# main.net
KiCad netlist of a schematic drawn in Altium Designer
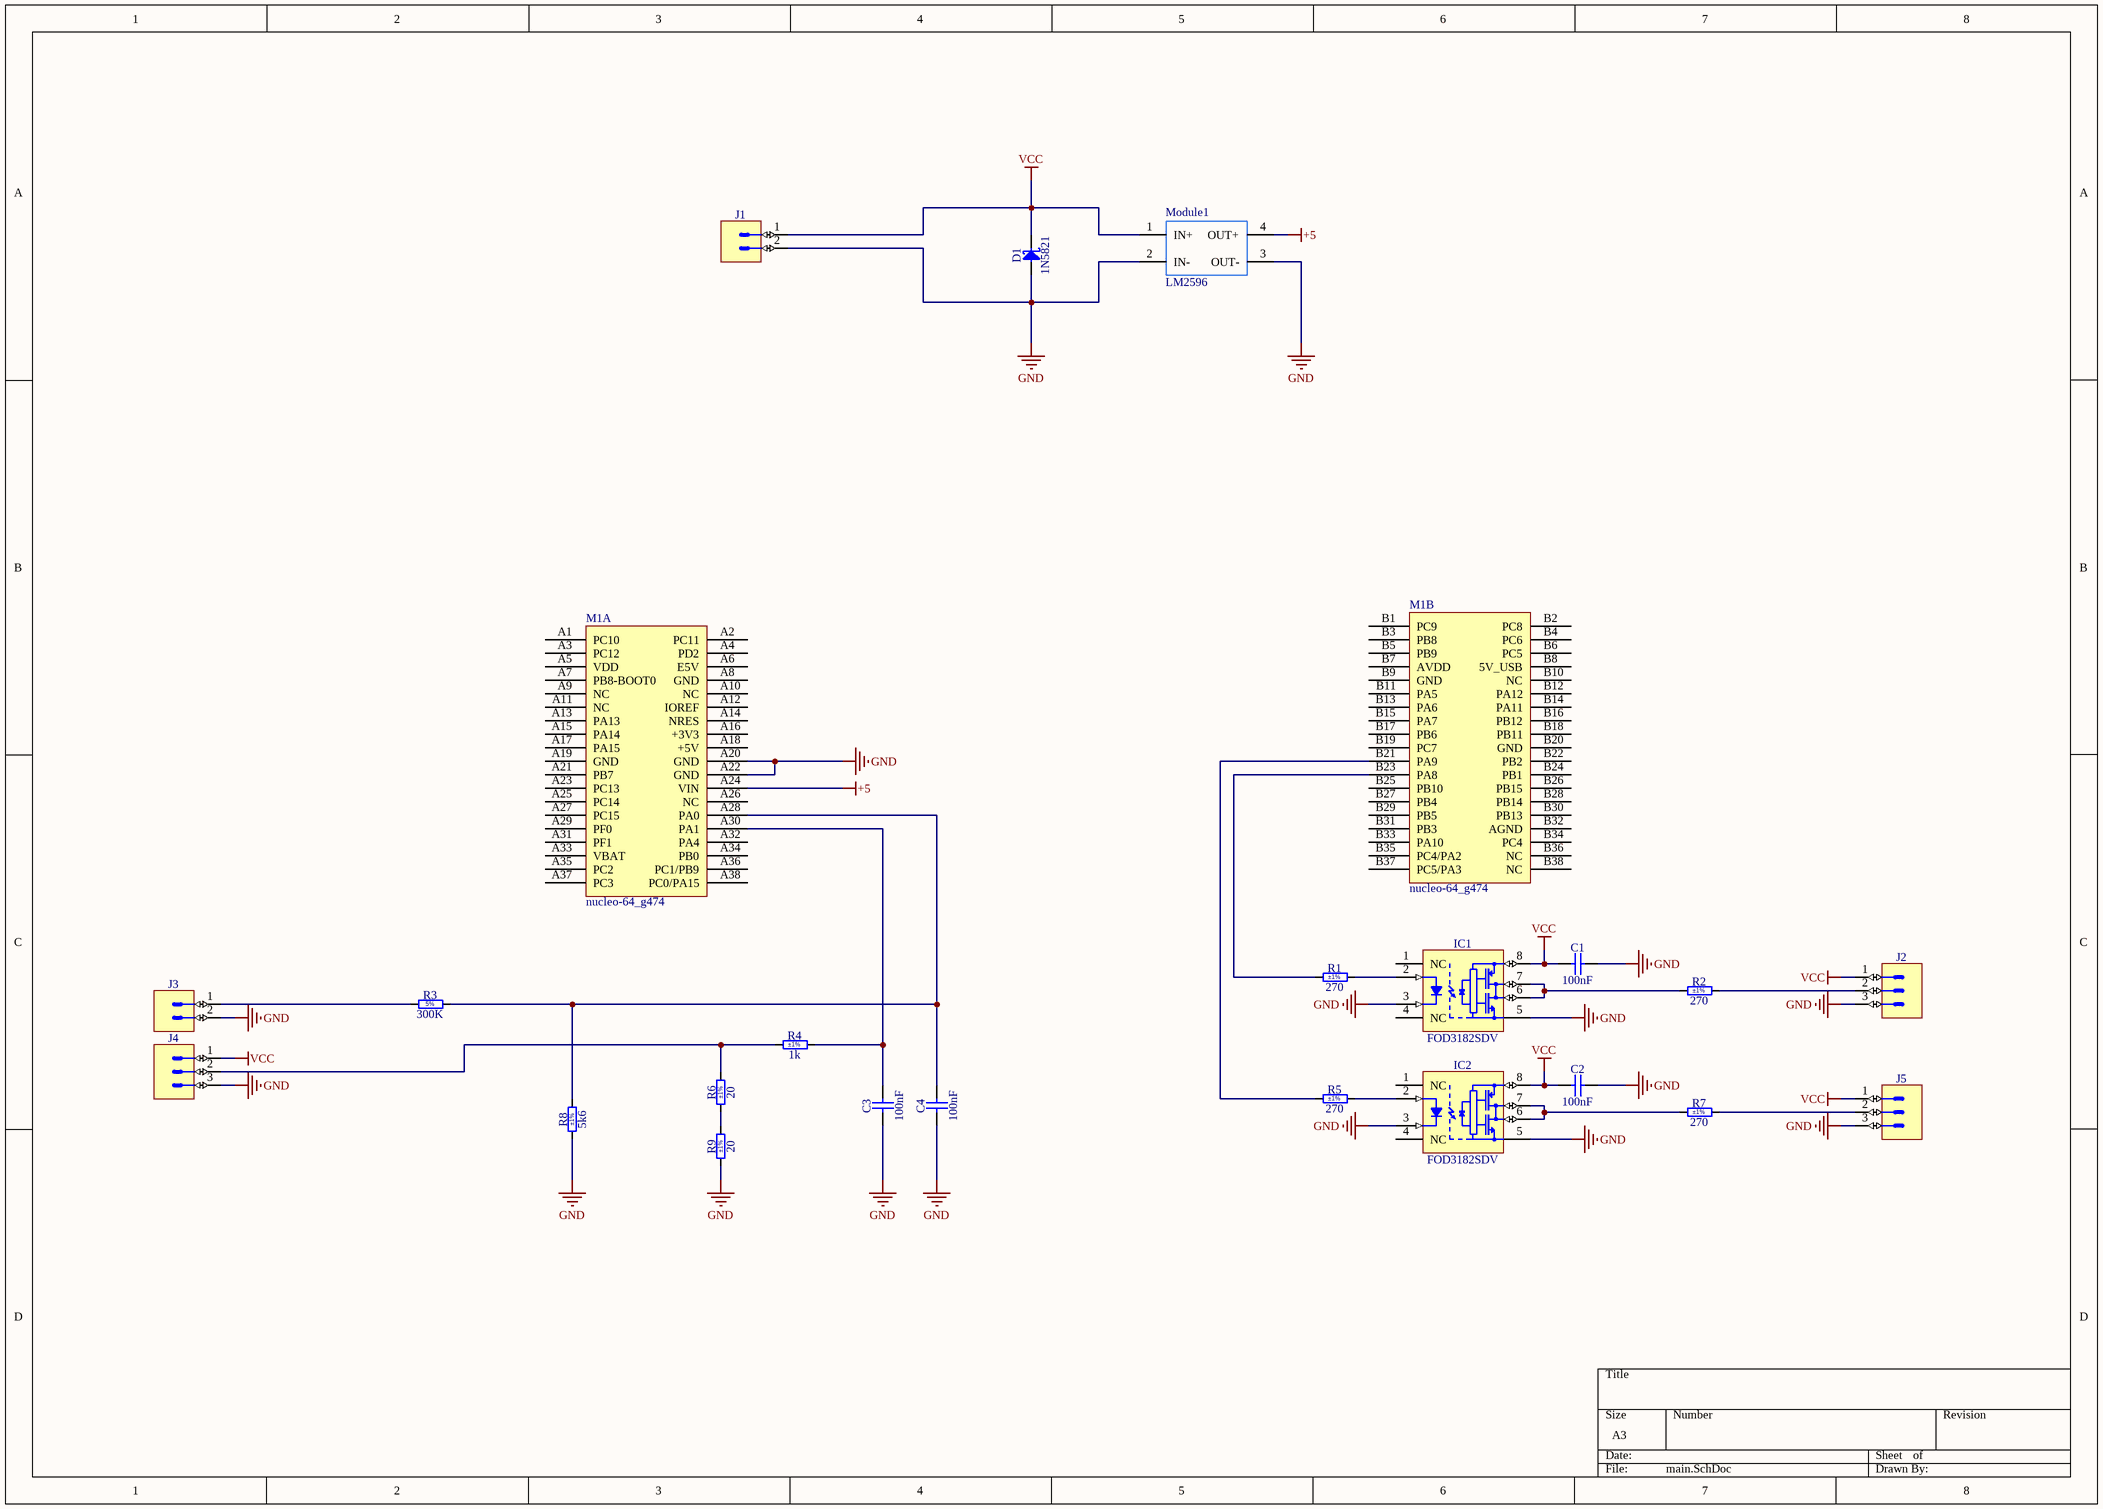
[diagram p0: main.SchDoc]

(export (version "E")
  (design (tool "Eeschema 10.0.6"))
  (components
    (comp (ref "C1")
      (value "100nF")
      (footprint "CAPRR508-350X500X500")
      (description "Non-polarised capacitor")
      (fields
        (field (name "PART NUMBER") "CCR_100NF_50V_10%_X7R_508-350X500X500")
        (field (name "VOLTAGE") "50VDC")
        (field (name "AUTHOR") "CERN DEM JLC")
      )
      (libsource (lib "Capacitors") (part "Capacitor - non polarized"))
    )
    (comp (ref "C2")
      (value "100nF")
      (footprint "CAPRR508-350X500X500")
      (description "Non-polarised capacitor")
      (fields
        (field (name "PART NUMBER") "CCR_100NF_50V_10%_X7R_508-350X500X500")
        (field (name "VOLTAGE") "50VDC")
        (field (name "AUTHOR") "CERN DEM JLC")
      )
      (libsource (lib "Capacitors") (part "Capacitor - non polarized"))
    )
    (comp (ref "C3")
      (value "100nF")
      (footprint "CAPRR508-350X500X500")
      (description "Non-polarised capacitor")
      (fields
        (field (name "PART NUMBER") "CCR_100NF_50V_10%_X7R_508-350X500X500")
        (field (name "VOLTAGE") "50VDC")
        (field (name "AUTHOR") "CERN DEM JLC")
      )
      (libsource (lib "Capacitors") (part "Capacitor - non polarized"))
    )
    (comp (ref "C4")
      (value "100nF")
      (footprint "CAPRR508-350X500X500")
      (description "Non-polarised capacitor")
      (fields
        (field (name "PART NUMBER") "CCR_100NF_50V_10%_X7R_508-350X500X500")
        (field (name "VOLTAGE") "50VDC")
        (field (name "AUTHOR") "CERN DEM JLC")
      )
      (libsource (lib "Capacitors") (part "Capacitor - non polarized"))
    )
    (comp (ref "D1")
      (value "1N5821")
      (footprint "DO-201AD")
      (description "Schottky Diode")
      (fields
        (field (name "VOLTAGE") "30V")
        (field (name "POWER") "3A")
        (field (name "AUTHOR") "CERN DEM JLC")
      )
      (libsource (lib "ICs And Semiconductors") (part "Diode Schottky"))
    )
    (comp (ref "IC1")
      (value "FOD3182SDV")
      (footprint "FAIRCHILD_8LD MDIP (OPTION S)")
      (description "Optocoupler")
      (fields (field (name "MANUFACTURER") "FAIRCHILD SEMICONDUCTOR") (field (name "AUTHOR") "CERN DEM JLC"))
      (libsource (lib "ICs And Semiconductors") (part "Optocoupler Type17"))
    )
    (comp (ref "IC2")
      (value "FOD3182SDV")
      (footprint "FAIRCHILD_8LD MDIP (OPTION S)")
      (description "Optocoupler")
      (fields (field (name "MANUFACTURER") "FAIRCHILD SEMICONDUCTOR") (field (name "AUTHOR") "CERN DEM JLC"))
      (libsource (lib "ICs And Semiconductors") (part "Optocoupler Type17"))
    )
    (comp (ref "J1")
      (value "~")
      (footprint "PHOENIX_1757242")
      (description "Connector 2 Male")
      (fields
        (field (name "PART NUMBER") "PHOENIX_1757242")
        (field (name "MANUFACTURER") "PHOENIX CONTACT")
        (field (name "AUTHOR") "CERN DEM JLC")
      )
      (libsource (lib "Connectors") (part "Connector 2 Male"))
    )
    (comp (ref "J2")
      (value "~")
      (footprint "PHOENIX_1757255")
      (description "Connector 3 Male")
      (fields
        (field (name "PART NUMBER") "PHOENIX_1757255")
        (field (name "MANUFACTURER") "PHOENIX CONTACT")
        (field (name "AUTHOR") "CERN DEM JLC")
      )
      (libsource (lib "") (part "Connector 3 Male_1"))
    )
    (comp (ref "J3")
      (value "~")
      (footprint "PHOENIX_1757242")
      (description "Connector 2 Male")
      (fields
        (field (name "PART NUMBER") "PHOENIX_1757242")
        (field (name "MANUFACTURER") "PHOENIX CONTACT")
        (field (name "AUTHOR") "CERN DEM JLC")
      )
      (libsource (lib "Connectors") (part "Connector 2 Male"))
    )
    (comp (ref "J4")
      (value "~")
      (footprint "PHOENIX_1757255")
      (description "Connector 3 Male")
      (fields
        (field (name "PART NUMBER") "PHOENIX_1757255")
        (field (name "MANUFACTURER") "PHOENIX CONTACT")
        (field (name "AUTHOR") "CERN DEM JLC")
      )
      (libsource (lib "Connectors") (part "Connector 3 Male"))
    )
    (comp (ref "J5")
      (value "~")
      (footprint "PHOENIX_1757255")
      (description "Connector 3 Male")
      (fields
        (field (name "PART NUMBER") "PHOENIX_1757255")
        (field (name "MANUFACTURER") "PHOENIX CONTACT")
        (field (name "AUTHOR") "CERN DEM JLC")
      )
      (libsource (lib "") (part "Connector 3 Male_1"))
    )
    (comp (ref "M1")
      (value "nucleo-64_g474")
      (footprint "nucleo-64_g474:nucleo-64_g474")
      (libsource (lib "nucleo-64_g474") (part "nucleo-64_g474"))
    )
    (comp (ref "Module1") (value "LM2596") (footprint "DC_DC:DCDC") (libsource (lib "DC_DC") (part "LM2596")))
    (comp (ref "R1")
      (value "270")
      (footprint "RES1016-630X250")
      (description "Resistor - 1%")
      (fields
        (field (name "TOLERANCE") "±1%")
        (field (name "PART NUMBER") "RMF_270R_1%_0.6W_50PPM_1016-630X250")
        (field (name "POWER") "0.6W")
        (field (name "AUTHOR") "CERN DEM JLC")
      )
      (libsource (lib "Resistors") (part "Resistor - 1%"))
    )
    (comp (ref "R2")
      (value "270")
      (footprint "RES1016-630X250")
      (description "Resistor - 1%")
      (fields
        (field (name "TOLERANCE") "±1%")
        (field (name "PART NUMBER") "RMF_270R_1%_0.6W_50PPM_1016-630X250")
        (field (name "POWER") "0.6W")
        (field (name "AUTHOR") "CERN DEM JLC")
      )
      (libsource (lib "Resistors") (part "Resistor - 1%"))
    )
    (comp (ref "R3")
      (value "300K")
      (footprint "RES_PANASONIC_ERG5S")
      (description "Resistor - 5%")
      (fields
        (field (name "PART NUMBER") "RMF_100K_5%_5W_200PPM_PANASONIC_ERG5SJ104")
        (field (name "POWER") "5W")
        (field (name "AUTHOR") "CERN DEM BC")
      )
      (libsource (lib "Resistors") (part "Resistor - 5%"))
    )
    (comp (ref "R4")
      (value "1k")
      (footprint "RES1016-630X250")
      (description "Resistor - 1%")
      (fields
        (field (name "TOLERANCE") "±1%")
        (field (name "PART NUMBER") "RMF_1K_1%_0.6W_50PPM_1016-630X250")
        (field (name "POWER") "0.6W")
        (field (name "AUTHOR") "CERN DEM JLC")
      )
      (libsource (lib "Resistors") (part "Resistor - 1%"))
    )
    (comp (ref "R5")
      (value "270")
      (footprint "RES1016-630X250")
      (description "Resistor - 1%")
      (fields
        (field (name "TOLERANCE") "±1%")
        (field (name "PART NUMBER") "RMF_270R_1%_0.6W_50PPM_1016-630X250")
        (field (name "POWER") "0.6W")
        (field (name "AUTHOR") "CERN DEM JLC")
      )
      (libsource (lib "Resistors") (part "Resistor - 1%"))
    )
    (comp (ref "R6")
      (value "20")
      (footprint "RES1016-630X250")
      (description "Resistor - 1%")
      (fields
        (field (name "TOLERANCE") "±1%")
        (field (name "PART NUMBER") "RMF_120R_1%_0.6W_50PPM_1016-630X250")
        (field (name "POWER") "0.6W")
        (field (name "AUTHOR") "CERN DEM JLC")
      )
      (libsource (lib "Resistors") (part "Resistor - 1%"))
    )
    (comp (ref "R7")
      (value "270")
      (footprint "RES1016-630X250")
      (description "Resistor - 1%")
      (fields
        (field (name "TOLERANCE") "±1%")
        (field (name "PART NUMBER") "RMF_270R_1%_0.6W_50PPM_1016-630X250")
        (field (name "POWER") "0.6W")
        (field (name "AUTHOR") "CERN DEM JLC")
      )
      (libsource (lib "Resistors") (part "Resistor - 1%"))
    )
    (comp (ref "R8")
      (value "5k6")
      (footprint "RES1016-630X250")
      (description "Resistor - 1%")
      (fields
        (field (name "TOLERANCE") "±1%")
        (field (name "PART NUMBER") "RMF_5K6_1%_0.6W_50PPM_1016-630X250")
        (field (name "POWER") "0.6W")
        (field (name "AUTHOR") "CERN DEM JLC")
      )
      (libsource (lib "Resistors") (part "Resistor - 1%"))
    )
    (comp (ref "R9")
      (value "20")
      (footprint "RES1016-630X250")
      (description "Resistor - 1%")
      (fields
        (field (name "TOLERANCE") "±1%")
        (field (name "PART NUMBER") "RMF_120R_1%_0.6W_50PPM_1016-630X250")
        (field (name "POWER") "0.6W")
        (field (name "AUTHOR") "CERN DEM JLC")
      )
      (libsource (lib "Resistors") (part "Resistor - 1%"))
    )
  )
  (nets
    (net (code "1") (name "+5") (class "Default")
      (node (ref "M1") (pin "A24") (pinfunction "VIN_A24") (pintype "passive"))
      (node (ref "Module1") (pin "4") (pinfunction "OUT+_4") (pintype "passive"))
    )
    (net (code "2") (name "GND") (class "Default")
      (node (ref "C1") (pin "2") (pinfunction "2_2") (pintype "passive"))
      (node (ref "C2") (pin "2") (pinfunction "2_2") (pintype "passive"))
      (node (ref "C3") (pin "1") (pinfunction "1_1") (pintype "passive"))
      (node (ref "C4") (pin "1") (pinfunction "1_1") (pintype "passive"))
      (node (ref "D1") (pin "2") (pinfunction "A_2") (pintype "passive"))
      (node (ref "IC1") (pin "3") (pinfunction "K_3") (pintype "input"))
      (node (ref "IC1") (pin "5") (pinfunction "VSS_5") (pintype "power_in"))
      (node (ref "IC2") (pin "3") (pinfunction "K_3") (pintype "input"))
      (node (ref "IC2") (pin "5") (pinfunction "VSS_5") (pintype "power_in"))
      (node (ref "J1") (pin "2") (pinfunction "2_2") (pintype "bidirectional"))
      (node (ref "J2") (pin "3") (pinfunction "3_3") (pintype "bidirectional"))
      (node (ref "J3") (pin "2") (pinfunction "2_2") (pintype "bidirectional"))
      (node (ref "J4") (pin "3") (pinfunction "3_3") (pintype "bidirectional"))
      (node (ref "J5") (pin "3") (pinfunction "3_3") (pintype "bidirectional"))
      (node (ref "M1") (pin "A20") (pinfunction "GND_A20") (pintype "passive"))
      (node (ref "M1") (pin "A22") (pinfunction "GND_A22") (pintype "passive"))
      (node (ref "Module1") (pin "2") (pinfunction "IN-_2") (pintype "passive"))
      (node (ref "Module1") (pin "3") (pinfunction "OUT-_3") (pintype "passive"))
      (node (ref "R8") (pin "1") (pinfunction "1_1") (pintype "passive"))
      (node (ref "R9") (pin "1") (pinfunction "1_1") (pintype "passive"))
    )
    (net (code "3") (name "Net-(IC1-A)") (class "Default")
      (node (ref "IC1") (pin "2") (pinfunction "A_2") (pintype "input"))
      (node (ref "R1") (pin "2") (pinfunction "2_2") (pintype "passive"))
    )
    (net (code "4") (name "Net-(IC1-VO1)") (class "Default")
      (node (ref "IC1") (pin "6") (pinfunction "VO1_6") (pintype "bidirectional"))
      (node (ref "IC1") (pin "7") (pinfunction "VO2_7") (pintype "bidirectional"))
      (node (ref "R2") (pin "1") (pinfunction "1_1") (pintype "passive"))
    )
    (net (code "5") (name "Net-(IC2-A)") (class "Default")
      (node (ref "IC2") (pin "2") (pinfunction "A_2") (pintype "input"))
      (node (ref "R5") (pin "2") (pinfunction "2_2") (pintype "passive"))
    )
    (net (code "6") (name "Net-(IC2-VO1)") (class "Default")
      (node (ref "IC2") (pin "6") (pinfunction "VO1_6") (pintype "bidirectional"))
      (node (ref "IC2") (pin "7") (pinfunction "VO2_7") (pintype "bidirectional"))
      (node (ref "R7") (pin "1") (pinfunction "1_1") (pintype "passive"))
    )
    (net (code "7") (name "Net-(J2-Pad2)") (class "Default")
      (node (ref "J2") (pin "2") (pinfunction "2_2") (pintype "bidirectional"))
      (node (ref "R2") (pin "2") (pinfunction "2_2") (pintype "passive"))
    )
    (net (code "8") (name "Net-(J3-Pad1)") (class "Default")
      (node (ref "J3") (pin "1") (pinfunction "1_1") (pintype "bidirectional"))
      (node (ref "R3") (pin "1") (pinfunction "1_1") (pintype "passive"))
    )
    (net (code "9") (name "Net-(J4-Pad2)") (class "Default")
      (node (ref "J4") (pin "2") (pinfunction "2_2") (pintype "bidirectional"))
      (node (ref "R4") (pin "1") (pinfunction "1_1") (pintype "passive"))
      (node (ref "R6") (pin "2") (pinfunction "2_2") (pintype "passive"))
    )
    (net (code "10") (name "Net-(J5-Pad2)") (class "Default")
      (node (ref "J5") (pin "2") (pinfunction "2_2") (pintype "bidirectional"))
      (node (ref "R7") (pin "2") (pinfunction "2_2") (pintype "passive"))
    )
    (net (code "11") (name "Net-(M1A-PA0)") (class "Default")
      (node (ref "C4") (pin "2") (pinfunction "2_2") (pintype "passive"))
      (node (ref "M1") (pin "A28") (pinfunction "PA0_A28") (pintype "passive"))
      (node (ref "R3") (pin "2") (pinfunction "2_2") (pintype "passive"))
      (node (ref "R8") (pin "2") (pinfunction "2_2") (pintype "passive"))
    )
    (net (code "12") (name "Net-(M1A-PA1)") (class "Default")
      (node (ref "C3") (pin "2") (pinfunction "2_2") (pintype "passive"))
      (node (ref "M1") (pin "A30") (pinfunction "PA1_A30") (pintype "passive"))
      (node (ref "R4") (pin "2") (pinfunction "2_2") (pintype "passive"))
    )
    (net (code "13") (name "Net-(M1B-PA8)") (class "Default")
      (node (ref "M1") (pin "B23") (pinfunction "PA8_B23") (pintype "passive"))
      (node (ref "R1") (pin "1") (pinfunction "1_1") (pintype "passive"))
    )
    (net (code "14") (name "Net-(M1B-PA9)") (class "Default")
      (node (ref "M1") (pin "B21") (pinfunction "PA9_B21") (pintype "passive"))
      (node (ref "R5") (pin "1") (pinfunction "1_1") (pintype "passive"))
    )
    (net (code "15") (name "Net-(R6-Pad1)") (class "Default")
      (node (ref "R6") (pin "1") (pinfunction "1_1") (pintype "passive"))
      (node (ref "R9") (pin "2") (pinfunction "2_2") (pintype "passive"))
    )
    (net (code "16") (name "VCC") (class "Default")
      (node (ref "C1") (pin "1") (pinfunction "1_1") (pintype "passive"))
      (node (ref "C2") (pin "1") (pinfunction "1_1") (pintype "passive"))
      (node (ref "D1") (pin "1") (pinfunction "C_1") (pintype "passive"))
      (node (ref "IC1") (pin "8") (pinfunction "VDD_8") (pintype "bidirectional"))
      (node (ref "IC2") (pin "8") (pinfunction "VDD_8") (pintype "bidirectional"))
      (node (ref "J1") (pin "1") (pinfunction "1_1") (pintype "bidirectional"))
      (node (ref "J2") (pin "1") (pinfunction "1_1") (pintype "bidirectional"))
      (node (ref "J4") (pin "1") (pinfunction "1_1") (pintype "bidirectional"))
      (node (ref "J5") (pin "1") (pinfunction "1_1") (pintype "bidirectional"))
      (node (ref "Module1") (pin "1") (pinfunction "IN+_1") (pintype "passive"))
    )
    (net (code "17") (name "unconnected-(IC1-NC-Pad1)") (class "Default")
      (node (ref "IC1") (pin "1") (pinfunction "NC_1") (pintype "power_in"))
    )
    (net (code "18") (name "unconnected-(IC1-NC-Pad4)") (class "Default")
      (node (ref "IC1") (pin "4") (pinfunction "NC_4") (pintype "passive"))
    )
    (net (code "19") (name "unconnected-(IC2-NC-Pad1)") (class "Default")
      (node (ref "IC2") (pin "1") (pinfunction "NC_1") (pintype "power_in"))
    )
    (net (code "20") (name "unconnected-(IC2-NC-Pad4)") (class "Default")
      (node (ref "IC2") (pin "4") (pinfunction "NC_4") (pintype "passive"))
    )
    (net (code "21") (name "unconnected-(M1A-+3V3-PadA16)") (class "Default")
      (node (ref "M1") (pin "A16") (pinfunction "+3V3_A16") (pintype "passive"))
    )
    (net (code "22") (name "unconnected-(M1A-+5V-PadA18)") (class "Default")
      (node (ref "M1") (pin "A18") (pinfunction "+5V_A18") (pintype "passive"))
    )
    (net (code "23") (name "unconnected-(M1A-E5V-PadA6)") (class "Default")
      (node (ref "M1") (pin "A6") (pinfunction "E5V_A6") (pintype "passive"))
    )
    (net (code "24") (name "unconnected-(M1A-GND-PadA8)") (class "Default")
      (node (ref "M1") (pin "A8") (pinfunction "GND_A8") (pintype "passive"))
    )
    (net (code "25") (name "unconnected-(M1A-GND-PadA19)") (class "Default")
      (node (ref "M1") (pin "A19") (pinfunction "GND_A19") (pintype "passive"))
    )
    (net (code "26") (name "unconnected-(M1A-IOREF-PadA12)") (class "Default")
      (node (ref "M1") (pin "A12") (pinfunction "IOREF_A12") (pintype "passive"))
    )
    (net (code "27") (name "unconnected-(M1A-NC-PadA9)") (class "Default")
      (node (ref "M1") (pin "A9") (pinfunction "NC_A9") (pintype "passive"))
    )
    (net (code "28") (name "unconnected-(M1A-NC-PadA10)") (class "Default")
      (node (ref "M1") (pin "A10") (pinfunction "NC_A10") (pintype "passive"))
    )
    (net (code "29") (name "unconnected-(M1A-NC-PadA11)") (class "Default")
      (node (ref "M1") (pin "A11") (pinfunction "NC_A11") (pintype "passive"))
    )
    (net (code "30") (name "unconnected-(M1A-NC-PadA26)") (class "Default")
      (node (ref "M1") (pin "A26") (pinfunction "NC_A26") (pintype "passive"))
    )
    (net (code "31") (name "unconnected-(M1A-NRES-PadA14)") (class "Default")
      (node (ref "M1") (pin "A14") (pinfunction "NRES_A14") (pintype "passive"))
    )
    (net (code "32") (name "unconnected-(M1A-PA4-PadA32)") (class "Default")
      (node (ref "M1") (pin "A32") (pinfunction "PA4_A32") (pintype "passive"))
    )
    (net (code "33") (name "unconnected-(M1A-PA13-PadA13)") (class "Default")
      (node (ref "M1") (pin "A13") (pinfunction "PA13_A13") (pintype "passive"))
    )
    (net (code "34") (name "unconnected-(M1A-PA14-PadA15)") (class "Default")
      (node (ref "M1") (pin "A15") (pinfunction "PA14_A15") (pintype "passive"))
    )
    (net (code "35") (name "unconnected-(M1A-PA15-PadA17)") (class "Default")
      (node (ref "M1") (pin "A17") (pinfunction "PA15_A17") (pintype "passive"))
    )
    (net (code "36") (name "unconnected-(M1A-PB0-PadA34)") (class "Default")
      (node (ref "M1") (pin "A34") (pinfunction "PB0_A34") (pintype "passive"))
    )
    (net (code "37") (name "unconnected-(M1A-PB7-PadA21)") (class "Default")
      (node (ref "M1") (pin "A21") (pinfunction "PB7_A21") (pintype "passive"))
    )
    (net (code "38") (name "unconnected-(M1A-PB8-BOOT0-PadA7)") (class "Default")
      (node (ref "M1") (pin "A7") (pinfunction "PB8-BOOT0_A7") (pintype "passive"))
    )
    (net (code "39") (name "unconnected-(M1A-PC0{slash}PA15-PadA38)") (class "Default")
      (node (ref "M1") (pin "A38") (pinfunction "PC0/PA15_A38") (pintype "passive"))
    )
    (net (code "40") (name "unconnected-(M1A-PC1{slash}PB9-PadA36)") (class "Default")
      (node (ref "M1") (pin "A36") (pinfunction "PC1/PB9_A36") (pintype "passive"))
    )
    (net (code "41") (name "unconnected-(M1A-PC2-PadA35)") (class "Default")
      (node (ref "M1") (pin "A35") (pinfunction "PC2_A35") (pintype "passive"))
    )
    (net (code "42") (name "unconnected-(M1A-PC3-PadA37)") (class "Default")
      (node (ref "M1") (pin "A37") (pinfunction "PC3_A37") (pintype "passive"))
    )
    (net (code "43") (name "unconnected-(M1A-PC10-PadA1)") (class "Default")
      (node (ref "M1") (pin "A1") (pinfunction "PC10_A1") (pintype "passive"))
    )
    (net (code "44") (name "unconnected-(M1A-PC11-PadA2)") (class "Default")
      (node (ref "M1") (pin "A2") (pinfunction "PC11_A2") (pintype "passive"))
    )
    (net (code "45") (name "unconnected-(M1A-PC12-PadA3)") (class "Default")
      (node (ref "M1") (pin "A3") (pinfunction "PC12_A3") (pintype "passive"))
    )
    (net (code "46") (name "unconnected-(M1A-PC13-PadA23)") (class "Default")
      (node (ref "M1") (pin "A23") (pinfunction "PC13_A23") (pintype "passive"))
    )
    (net (code "47") (name "unconnected-(M1A-PC14-PadA25)") (class "Default")
      (node (ref "M1") (pin "A25") (pinfunction "PC14_A25") (pintype "passive"))
    )
    (net (code "48") (name "unconnected-(M1A-PC15-PadA27)") (class "Default")
      (node (ref "M1") (pin "A27") (pinfunction "PC15_A27") (pintype "passive"))
    )
    (net (code "49") (name "unconnected-(M1A-PD2-PadA4)") (class "Default")
      (node (ref "M1") (pin "A4") (pinfunction "PD2_A4") (pintype "passive"))
    )
    (net (code "50") (name "unconnected-(M1A-PF0-PadA29)") (class "Default")
      (node (ref "M1") (pin "A29") (pinfunction "PF0_A29") (pintype "passive"))
    )
    (net (code "51") (name "unconnected-(M1A-PF1-PadA31)") (class "Default")
      (node (ref "M1") (pin "A31") (pinfunction "PF1_A31") (pintype "passive"))
    )
    (net (code "52") (name "unconnected-(M1A-VBAT-PadA33)") (class "Default")
      (node (ref "M1") (pin "A33") (pinfunction "VBAT_A33") (pintype "passive"))
    )
    (net (code "53") (name "unconnected-(M1A-VDD-PadA5)") (class "Default")
      (node (ref "M1") (pin "A5") (pinfunction "VDD_A5") (pintype "passive"))
    )
    (net (code "54") (name "unconnected-(M1B-5V_USB-PadB8)") (class "Default")
      (node (ref "M1") (pin "B8") (pinfunction "5V_USB_B8") (pintype "passive"))
    )
    (net (code "55") (name "unconnected-(M1B-AGND-PadB32)") (class "Default")
      (node (ref "M1") (pin "B32") (pinfunction "AGND_B32") (pintype "passive"))
    )
    (net (code "56") (name "unconnected-(M1B-AVDD-PadB7)") (class "Default")
      (node (ref "M1") (pin "B7") (pinfunction "AVDD_B7") (pintype "passive"))
    )
    (net (code "57") (name "unconnected-(M1B-GND-PadB9)") (class "Default")
      (node (ref "M1") (pin "B9") (pinfunction "GND_B9") (pintype "passive"))
    )
    (net (code "58") (name "unconnected-(M1B-GND-PadB20)") (class "Default")
      (node (ref "M1") (pin "B20") (pinfunction "GND_B20") (pintype "passive"))
    )
    (net (code "59") (name "unconnected-(M1B-NC-PadB10)") (class "Default")
      (node (ref "M1") (pin "B10") (pinfunction "NC_B10") (pintype "passive"))
    )
    (net (code "60") (name "unconnected-(M1B-NC-PadB36)") (class "Default")
      (node (ref "M1") (pin "B36") (pinfunction "NC_B36") (pintype "passive"))
    )
    (net (code "61") (name "unconnected-(M1B-NC-PadB38)") (class "Default")
      (node (ref "M1") (pin "B38") (pinfunction "NC_B38") (pintype "passive"))
    )
    (net (code "62") (name "unconnected-(M1B-PA5-PadB11)") (class "Default")
      (node (ref "M1") (pin "B11") (pinfunction "PA5_B11") (pintype "passive"))
    )
    (net (code "63") (name "unconnected-(M1B-PA6-PadB13)") (class "Default")
      (node (ref "M1") (pin "B13") (pinfunction "PA6_B13") (pintype "passive"))
    )
    (net (code "64") (name "unconnected-(M1B-PA7-PadB15)") (class "Default")
      (node (ref "M1") (pin "B15") (pinfunction "PA7_B15") (pintype "passive"))
    )
    (net (code "65") (name "unconnected-(M1B-PA10-PadB33)") (class "Default")
      (node (ref "M1") (pin "B33") (pinfunction "PA10_B33") (pintype "passive"))
    )
    (net (code "66") (name "unconnected-(M1B-PA11-PadB14)") (class "Default")
      (node (ref "M1") (pin "B14") (pinfunction "PA11_B14") (pintype "passive"))
    )
    (net (code "67") (name "unconnected-(M1B-PA12-PadB12)") (class "Default")
      (node (ref "M1") (pin "B12") (pinfunction "PA12_B12") (pintype "passive"))
    )
    (net (code "68") (name "unconnected-(M1B-PB1-PadB24)") (class "Default")
      (node (ref "M1") (pin "B24") (pinfunction "PB1_B24") (pintype "passive"))
    )
    (net (code "69") (name "unconnected-(M1B-PB2-PadB22)") (class "Default")
      (node (ref "M1") (pin "B22") (pinfunction "PB2_B22") (pintype "passive"))
    )
    (net (code "70") (name "unconnected-(M1B-PB3-PadB31)") (class "Default")
      (node (ref "M1") (pin "B31") (pinfunction "PB3_B31") (pintype "passive"))
    )
    (net (code "71") (name "unconnected-(M1B-PB4-PadB27)") (class "Default")
      (node (ref "M1") (pin "B27") (pinfunction "PB4_B27") (pintype "passive"))
    )
    (net (code "72") (name "unconnected-(M1B-PB5-PadB29)") (class "Default")
      (node (ref "M1") (pin "B29") (pinfunction "PB5_B29") (pintype "passive"))
    )
    (net (code "73") (name "unconnected-(M1B-PB6-PadB17)") (class "Default")
      (node (ref "M1") (pin "B17") (pinfunction "PB6_B17") (pintype "passive"))
    )
    (net (code "74") (name "unconnected-(M1B-PB8-PadB3)") (class "Default")
      (node (ref "M1") (pin "B3") (pinfunction "PB8_B3") (pintype "passive"))
    )
    (net (code "75") (name "unconnected-(M1B-PB9-PadB5)") (class "Default")
      (node (ref "M1") (pin "B5") (pinfunction "PB9_B5") (pintype "passive"))
    )
    (net (code "76") (name "unconnected-(M1B-PB10-PadB25)") (class "Default")
      (node (ref "M1") (pin "B25") (pinfunction "PB10_B25") (pintype "passive"))
    )
    (net (code "77") (name "unconnected-(M1B-PB11-PadB18)") (class "Default")
      (node (ref "M1") (pin "B18") (pinfunction "PB11_B18") (pintype "passive"))
    )
    (net (code "78") (name "unconnected-(M1B-PB12-PadB16)") (class "Default")
      (node (ref "M1") (pin "B16") (pinfunction "PB12_B16") (pintype "passive"))
    )
    (net (code "79") (name "unconnected-(M1B-PB13-PadB30)") (class "Default")
      (node (ref "M1") (pin "B30") (pinfunction "PB13_B30") (pintype "passive"))
    )
    (net (code "80") (name "unconnected-(M1B-PB14-PadB28)") (class "Default")
      (node (ref "M1") (pin "B28") (pinfunction "PB14_B28") (pintype "passive"))
    )
    (net (code "81") (name "unconnected-(M1B-PB15-PadB26)") (class "Default")
      (node (ref "M1") (pin "B26") (pinfunction "PB15_B26") (pintype "passive"))
    )
    (net (code "82") (name "unconnected-(M1B-PC4-PadB34)") (class "Default")
      (node (ref "M1") (pin "B34") (pinfunction "PC4_B34") (pintype "passive"))
    )
    (net (code "83") (name "unconnected-(M1B-PC4{slash}PA2-PadB35)") (class "Default")
      (node (ref "M1") (pin "B35") (pinfunction "PC4/PA2_B35") (pintype "passive"))
    )
    (net (code "84") (name "unconnected-(M1B-PC5-PadB6)") (class "Default")
      (node (ref "M1") (pin "B6") (pinfunction "PC5_B6") (pintype "passive"))
    )
    (net (code "85") (name "unconnected-(M1B-PC5{slash}PA3-PadB37)") (class "Default")
      (node (ref "M1") (pin "B37") (pinfunction "PC5/PA3_B37") (pintype "passive"))
    )
    (net (code "86") (name "unconnected-(M1B-PC6-PadB4)") (class "Default")
      (node (ref "M1") (pin "B4") (pinfunction "PC6_B4") (pintype "passive"))
    )
    (net (code "87") (name "unconnected-(M1B-PC7-PadB19)") (class "Default")
      (node (ref "M1") (pin "B19") (pinfunction "PC7_B19") (pintype "passive"))
    )
    (net (code "88") (name "unconnected-(M1B-PC8-PadB2)") (class "Default")
      (node (ref "M1") (pin "B2") (pinfunction "PC8_B2") (pintype "passive"))
    )
    (net (code "89") (name "unconnected-(M1B-PC9-PadB1)") (class "Default")
      (node (ref "M1") (pin "B1") (pinfunction "PC9_B1") (pintype "passive"))
    )
  )
)
